# DDR3.net
KiCad netlist of a schematic drawn in Altium Designer
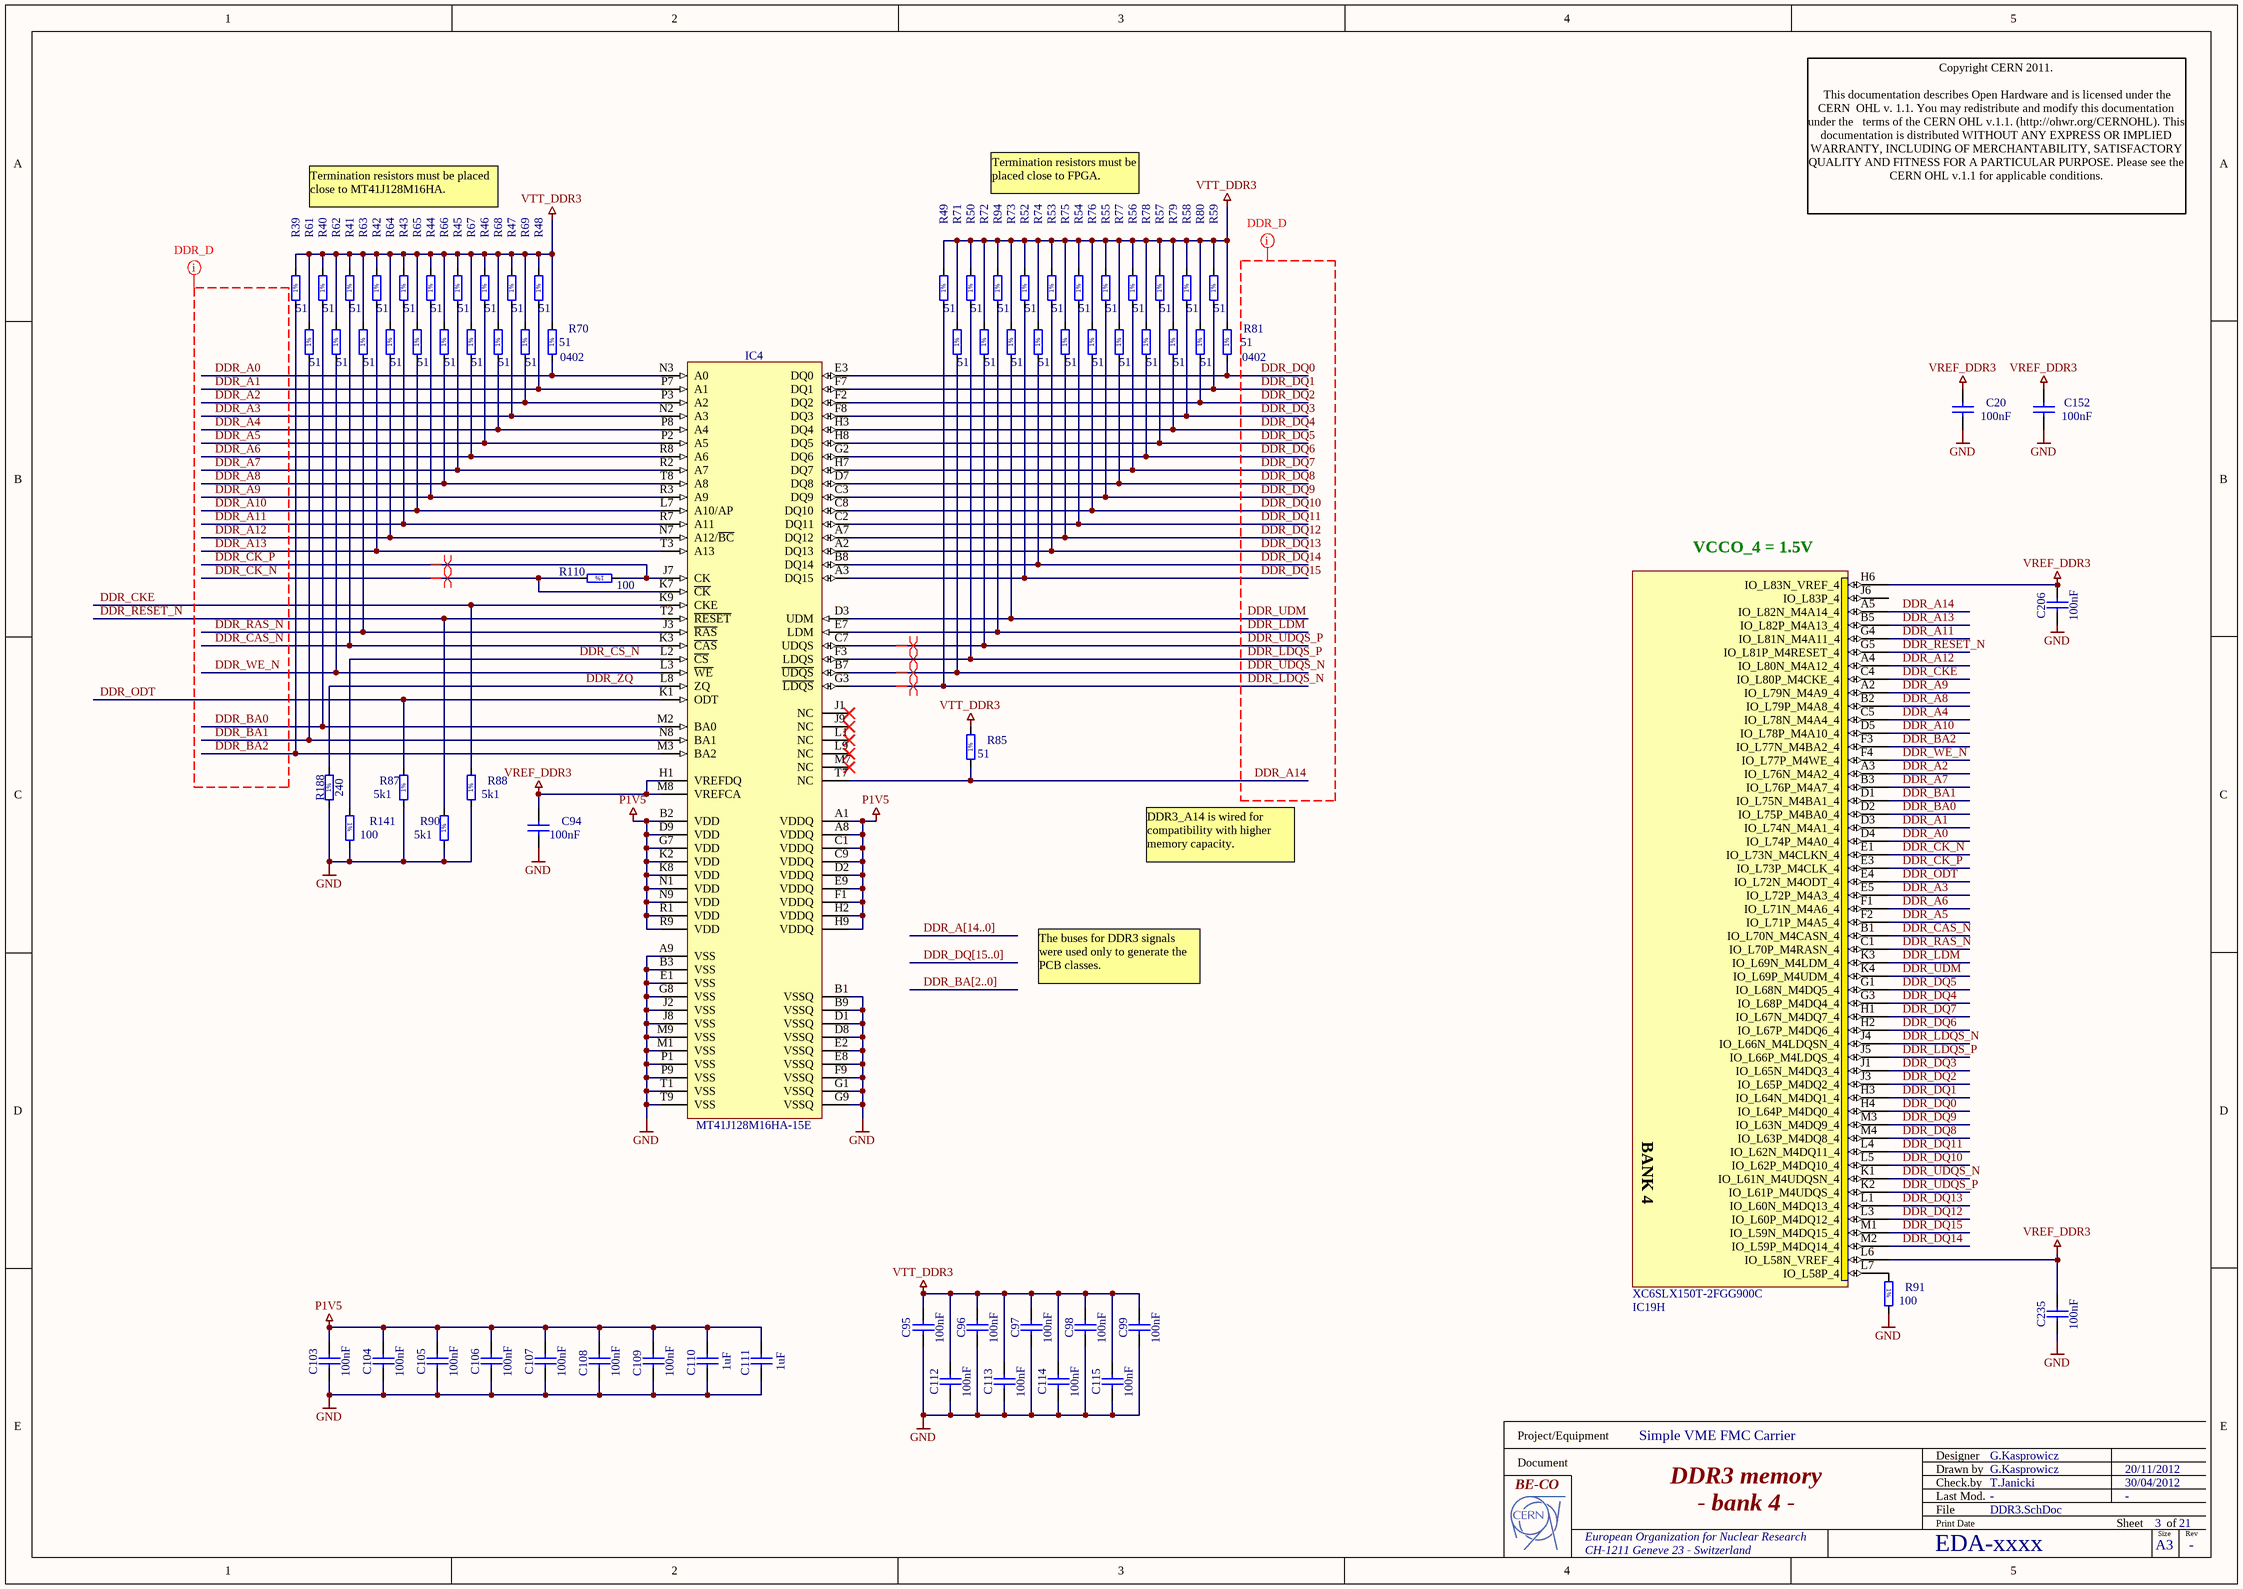
[diagram p0: DDR3.SchDoc]

(export (version "E")
  (design (tool "Eeschema 10.0.6"))
  (components
    (comp (ref "C20")
      (value "100nF")
      (footprint "CAPC1005X55N")
      (description "Non-polarised capacitor")
      (fields
        (field (name "PART NUMBER") "CC0402_100NF_16V_10%_X7R")
        (field (name "VOLTAGE") "16V")
        (field (name "AUTHOR") "CERN DEM JLC")
      )
      (libsource (lib "Capacitors") (part "Capacitor - non polarized"))
    )
    (comp (ref "C94")
      (value "100nF")
      (footprint "CAPC1005X55N")
      (description "Non-polarised capacitor")
      (fields
        (field (name "PART NUMBER") "CC0402_100NF_16V_10%_X7R")
        (field (name "VOLTAGE") "16V")
        (field (name "AUTHOR") "CERN DEM JLC")
      )
      (libsource (lib "Capacitors") (part "Capacitor - non polarized"))
    )
    (comp (ref "C95")
      (value "100nF")
      (footprint "CAPC1005X55N")
      (description "Non-polarised capacitor")
      (fields
        (field (name "PART NUMBER") "CC0402_100NF_16V_10%_X7R")
        (field (name "VOLTAGE") "16V")
        (field (name "AUTHOR") "CERN DEM JLC")
      )
      (libsource (lib "Capacitors") (part "Capacitor - non polarized"))
    )
    (comp (ref "C96")
      (value "100nF")
      (footprint "CAPC1005X55N")
      (description "Non-polarised capacitor")
      (fields
        (field (name "PART NUMBER") "CC0402_100NF_16V_10%_X7R")
        (field (name "VOLTAGE") "16V")
        (field (name "AUTHOR") "CERN DEM JLC")
      )
      (libsource (lib "Capacitors") (part "Capacitor - non polarized"))
    )
    (comp (ref "C97")
      (value "100nF")
      (footprint "CAPC1005X55N")
      (description "Non-polarised capacitor")
      (fields
        (field (name "PART NUMBER") "CC0402_100NF_16V_10%_X7R")
        (field (name "VOLTAGE") "16V")
        (field (name "AUTHOR") "CERN DEM JLC")
      )
      (libsource (lib "Capacitors") (part "Capacitor - non polarized"))
    )
    (comp (ref "C98")
      (value "100nF")
      (footprint "CAPC1005X55N")
      (description "Non-polarised capacitor")
      (fields
        (field (name "PART NUMBER") "CC0402_100NF_16V_10%_X7R")
        (field (name "VOLTAGE") "16V")
        (field (name "AUTHOR") "CERN DEM JLC")
      )
      (libsource (lib "Capacitors") (part "Capacitor - non polarized"))
    )
    (comp (ref "C99")
      (value "100nF")
      (footprint "CAPC1005X55N")
      (description "Non-polarised capacitor")
      (fields
        (field (name "PART NUMBER") "CC0402_100NF_16V_10%_X7R")
        (field (name "VOLTAGE") "16V")
        (field (name "AUTHOR") "CERN DEM JLC")
      )
      (libsource (lib "Capacitors") (part "Capacitor - non polarized"))
    )
    (comp (ref "C103")
      (value "100nF")
      (footprint "CAPC1005X55N")
      (description "Non-polarised capacitor")
      (fields
        (field (name "PART NUMBER") "CC0402_100NF_16V_10%_X7R")
        (field (name "VOLTAGE") "16V")
        (field (name "AUTHOR") "CERN DEM JLC")
      )
      (libsource (lib "Capacitors") (part "Capacitor - non polarized"))
    )
    (comp (ref "C104")
      (value "100nF")
      (footprint "CAPC1005X55N")
      (description "Non-polarised capacitor")
      (fields
        (field (name "PART NUMBER") "CC0402_100NF_16V_10%_X7R")
        (field (name "VOLTAGE") "16V")
        (field (name "AUTHOR") "CERN DEM JLC")
      )
      (libsource (lib "Capacitors") (part "Capacitor - non polarized"))
    )
    (comp (ref "C105")
      (value "100nF")
      (footprint "CAPC1005X55N")
      (description "Non-polarised capacitor")
      (fields
        (field (name "PART NUMBER") "CC0402_100NF_16V_10%_X7R")
        (field (name "VOLTAGE") "16V")
        (field (name "AUTHOR") "CERN DEM JLC")
      )
      (libsource (lib "Capacitors") (part "Capacitor - non polarized"))
    )
    (comp (ref "C106")
      (value "100nF")
      (footprint "CAPC1005X55N")
      (description "Non-polarised capacitor")
      (fields
        (field (name "PART NUMBER") "CC0402_100NF_16V_10%_X7R")
        (field (name "VOLTAGE") "16V")
        (field (name "AUTHOR") "CERN DEM JLC")
      )
      (libsource (lib "Capacitors") (part "Capacitor - non polarized"))
    )
    (comp (ref "C107")
      (value "100nF")
      (footprint "CAPC1005X55N")
      (description "Non-polarised capacitor")
      (fields
        (field (name "PART NUMBER") "CC0402_100NF_16V_10%_X7R")
        (field (name "VOLTAGE") "16V")
        (field (name "AUTHOR") "CERN DEM JLC")
      )
      (libsource (lib "Capacitors") (part "Capacitor - non polarized"))
    )
    (comp (ref "C108")
      (value "100nF")
      (footprint "CAPC1005X55N")
      (description "Non-polarised capacitor")
      (fields
        (field (name "PART NUMBER") "CC0402_100NF_16V_10%_X7R")
        (field (name "VOLTAGE") "16V")
        (field (name "AUTHOR") "CERN DEM JLC")
      )
      (libsource (lib "Capacitors") (part "Capacitor - non polarized"))
    )
    (comp (ref "C109")
      (value "100nF")
      (footprint "CAPC1005X55N")
      (description "Non-polarised capacitor")
      (fields
        (field (name "PART NUMBER") "CC0402_100NF_16V_10%_X7R")
        (field (name "VOLTAGE") "16V")
        (field (name "AUTHOR") "CERN DEM JLC")
      )
      (libsource (lib "Capacitors") (part "Capacitor - non polarized"))
    )
    (comp (ref "C110")
      (value "1uF")
      (footprint "CAPC1608X87N")
      (description "Non-polarised capacitor")
      (fields
        (field (name "PART NUMBER") "CC0603_1UF_16V_10%_X7R")
        (field (name "VOLTAGE") "16V")
        (field (name "AUTHOR") "CERN DEM JLC")
      )
      (libsource (lib "Capacitors") (part "Capacitor - non polarized"))
    )
    (comp (ref "C111")
      (value "1uF")
      (footprint "CAPC1608X87N")
      (description "Non-polarised capacitor")
      (fields
        (field (name "PART NUMBER") "CC0603_1UF_16V_10%_X7R")
        (field (name "VOLTAGE") "16V")
        (field (name "AUTHOR") "CERN DEM JLC")
      )
      (libsource (lib "Capacitors") (part "Capacitor - non polarized"))
    )
    (comp (ref "C112")
      (value "100nF")
      (footprint "CAPC1005X55N")
      (description "Non-polarised capacitor")
      (fields
        (field (name "PART NUMBER") "CC0402_100NF_16V_10%_X7R")
        (field (name "VOLTAGE") "16V")
        (field (name "AUTHOR") "CERN DEM JLC")
      )
      (libsource (lib "Capacitors") (part "Capacitor - non polarized"))
    )
    (comp (ref "C113")
      (value "100nF")
      (footprint "CAPC1005X55N")
      (description "Non-polarised capacitor")
      (fields
        (field (name "PART NUMBER") "CC0402_100NF_16V_10%_X7R")
        (field (name "VOLTAGE") "16V")
        (field (name "AUTHOR") "CERN DEM JLC")
      )
      (libsource (lib "Capacitors") (part "Capacitor - non polarized"))
    )
    (comp (ref "C114")
      (value "100nF")
      (footprint "CAPC1005X55N")
      (description "Non-polarised capacitor")
      (fields
        (field (name "PART NUMBER") "CC0402_100NF_16V_10%_X7R")
        (field (name "VOLTAGE") "16V")
        (field (name "AUTHOR") "CERN DEM JLC")
      )
      (libsource (lib "Capacitors") (part "Capacitor - non polarized"))
    )
    (comp (ref "C115")
      (value "100nF")
      (footprint "CAPC1005X55N")
      (description "Non-polarised capacitor")
      (fields
        (field (name "PART NUMBER") "CC0402_100NF_16V_10%_X7R")
        (field (name "VOLTAGE") "16V")
        (field (name "AUTHOR") "CERN DEM JLC")
      )
      (libsource (lib "Capacitors") (part "Capacitor - non polarized"))
    )
    (comp (ref "C152")
      (value "100nF")
      (footprint "CAPC1005X55N")
      (description "Non-polarised capacitor")
      (fields
        (field (name "PART NUMBER") "CC0402_100NF_16V_10%_X7R")
        (field (name "VOLTAGE") "16V")
        (field (name "AUTHOR") "CERN DEM JLC")
      )
      (libsource (lib "Capacitors") (part "Capacitor - non polarized"))
    )
    (comp (ref "C206")
      (value "100nF")
      (footprint "CAPC1005X55N")
      (description "Non-polarised capacitor")
      (fields
        (field (name "PART NUMBER") "CC0402_100NF_16V_10%_X7R")
        (field (name "VOLTAGE") "16V")
        (field (name "AUTHOR") "CERN DEM JLC")
      )
      (libsource (lib "Capacitors") (part "Capacitor - non polarized"))
    )
    (comp (ref "C235")
      (value "100nF")
      (footprint "CAPC1005X55N")
      (description "Non-polarised capacitor")
      (fields
        (field (name "PART NUMBER") "CC0402_100NF_16V_10%_X7R")
        (field (name "VOLTAGE") "16V")
        (field (name "AUTHOR") "CERN DEM JLC")
      )
      (libsource (lib "Capacitors") (part "Capacitor - non polarized"))
    )
    (comp (ref "IC4")
      (value "MT41J128M16HA-15E")
      (footprint "BGA96C80P9X16_900X1400X120")
      (description "16 Meg x 16 x 8 Banks DDR3 SDRAM")
      (fields (field (name "MANUFACTURER") "MICRON TECHNOLOGY") (field (name "AUTHOR") "CERN DEM JLC"))
      (libsource (lib "ICs And Semiconductors") (part "MT41J128M16HA"))
    )
    (comp (ref "IC19")
      (value "XC6SLX150T-2FGG900C")
      (footprint "BGA900C100P30X30_3100X3100X260")
      (description "SPARTAN-6, FPGA, 900-Ball BGA, Commercial Grade, Pb-Free")
      (fields (field (name "MANUFACTURER") "XILINX") (field (name "AUTHOR") "CERN DEM JLC"))
      (libsource (lib "ICs And Semiconductors") (part "XC6SLX150T-2FGG900C"))
    )
    (comp (ref "R39")
      (value "51")
      (footprint "RESC1005X40N")
      (description "Resistor - 1%")
      (fields
        (field (name "PART NUMBER") "R0402_51R_1%_0.0625W_100PPM")
        (field (name "POWER") "0.0625W")
        (field (name "AUTHOR") "CERN DEM JLC")
      )
      (libsource (lib "Resistors") (part "Resistor - 1%"))
    )
    (comp (ref "R40")
      (value "51")
      (footprint "RESC1005X40N")
      (description "Resistor - 1%")
      (fields
        (field (name "PART NUMBER") "R0402_51R_1%_0.0625W_100PPM")
        (field (name "POWER") "0.0625W")
        (field (name "AUTHOR") "CERN DEM JLC")
      )
      (libsource (lib "Resistors") (part "Resistor - 1%"))
    )
    (comp (ref "R41")
      (value "51")
      (footprint "RESC1005X40N")
      (description "Resistor - 1%")
      (fields
        (field (name "PART NUMBER") "R0402_51R_1%_0.0625W_100PPM")
        (field (name "POWER") "0.0625W")
        (field (name "AUTHOR") "CERN DEM JLC")
      )
      (libsource (lib "Resistors") (part "Resistor - 1%"))
    )
    (comp (ref "R42")
      (value "51")
      (footprint "RESC1005X40N")
      (description "Resistor - 1%")
      (fields
        (field (name "PART NUMBER") "R0402_51R_1%_0.0625W_100PPM")
        (field (name "POWER") "0.0625W")
        (field (name "AUTHOR") "CERN DEM JLC")
      )
      (libsource (lib "Resistors") (part "Resistor - 1%"))
    )
    (comp (ref "R43")
      (value "51")
      (footprint "RESC1005X40N")
      (description "Resistor - 1%")
      (fields
        (field (name "PART NUMBER") "R0402_51R_1%_0.0625W_100PPM")
        (field (name "POWER") "0.0625W")
        (field (name "AUTHOR") "CERN DEM JLC")
      )
      (libsource (lib "Resistors") (part "Resistor - 1%"))
    )
    (comp (ref "R44")
      (value "51")
      (footprint "RESC1005X40N")
      (description "Resistor - 1%")
      (fields
        (field (name "PART NUMBER") "R0402_51R_1%_0.0625W_100PPM")
        (field (name "POWER") "0.0625W")
        (field (name "AUTHOR") "CERN DEM JLC")
      )
      (libsource (lib "Resistors") (part "Resistor - 1%"))
    )
    (comp (ref "R45")
      (value "51")
      (footprint "RESC1005X40N")
      (description "Resistor - 1%")
      (fields
        (field (name "PART NUMBER") "R0402_51R_1%_0.0625W_100PPM")
        (field (name "POWER") "0.0625W")
        (field (name "AUTHOR") "CERN DEM JLC")
      )
      (libsource (lib "Resistors") (part "Resistor - 1%"))
    )
    (comp (ref "R46")
      (value "51")
      (footprint "RESC1005X40N")
      (description "Resistor - 1%")
      (fields
        (field (name "PART NUMBER") "R0402_51R_1%_0.0625W_100PPM")
        (field (name "POWER") "0.0625W")
        (field (name "AUTHOR") "CERN DEM JLC")
      )
      (libsource (lib "Resistors") (part "Resistor - 1%"))
    )
    (comp (ref "R47")
      (value "51")
      (footprint "RESC1005X40N")
      (description "Resistor - 1%")
      (fields
        (field (name "PART NUMBER") "R0402_51R_1%_0.0625W_100PPM")
        (field (name "POWER") "0.0625W")
        (field (name "AUTHOR") "CERN DEM JLC")
      )
      (libsource (lib "Resistors") (part "Resistor - 1%"))
    )
    (comp (ref "R48")
      (value "51")
      (footprint "RESC1005X40N")
      (description "Resistor - 1%")
      (fields
        (field (name "PART NUMBER") "R0402_51R_1%_0.0625W_100PPM")
        (field (name "POWER") "0.0625W")
        (field (name "AUTHOR") "CERN DEM JLC")
      )
      (libsource (lib "Resistors") (part "Resistor - 1%"))
    )
    (comp (ref "R49")
      (value "51")
      (footprint "RESC1005X40N")
      (description "Resistor - 1%")
      (fields
        (field (name "PART NUMBER") "R0402_51R_1%_0.0625W_100PPM")
        (field (name "POWER") "0.0625W")
        (field (name "AUTHOR") "CERN DEM JLC")
      )
      (libsource (lib "Resistors") (part "Resistor - 1%"))
    )
    (comp (ref "R50")
      (value "51")
      (footprint "RESC1005X40N")
      (description "Resistor - 1%")
      (fields
        (field (name "PART NUMBER") "R0402_51R_1%_0.0625W_100PPM")
        (field (name "POWER") "0.0625W")
        (field (name "AUTHOR") "CERN DEM JLC")
      )
      (libsource (lib "Resistors") (part "Resistor - 1%"))
    )
    (comp (ref "R52")
      (value "51")
      (footprint "RESC1005X40N")
      (description "Resistor - 1%")
      (fields
        (field (name "PART NUMBER") "R0402_51R_1%_0.0625W_100PPM")
        (field (name "POWER") "0.0625W")
        (field (name "AUTHOR") "CERN DEM JLC")
      )
      (libsource (lib "Resistors") (part "Resistor - 1%"))
    )
    (comp (ref "R53")
      (value "51")
      (footprint "RESC1005X40N")
      (description "Resistor - 1%")
      (fields
        (field (name "PART NUMBER") "R0402_51R_1%_0.0625W_100PPM")
        (field (name "POWER") "0.0625W")
        (field (name "AUTHOR") "CERN DEM JLC")
      )
      (libsource (lib "Resistors") (part "Resistor - 1%"))
    )
    (comp (ref "R54")
      (value "51")
      (footprint "RESC1005X40N")
      (description "Resistor - 1%")
      (fields
        (field (name "PART NUMBER") "R0402_51R_1%_0.0625W_100PPM")
        (field (name "POWER") "0.0625W")
        (field (name "AUTHOR") "CERN DEM JLC")
      )
      (libsource (lib "Resistors") (part "Resistor - 1%"))
    )
    (comp (ref "R55")
      (value "51")
      (footprint "RESC1005X40N")
      (description "Resistor - 1%")
      (fields
        (field (name "PART NUMBER") "R0402_51R_1%_0.0625W_100PPM")
        (field (name "POWER") "0.0625W")
        (field (name "AUTHOR") "CERN DEM JLC")
      )
      (libsource (lib "Resistors") (part "Resistor - 1%"))
    )
    (comp (ref "R56")
      (value "51")
      (footprint "RESC1005X40N")
      (description "Resistor - 1%")
      (fields
        (field (name "PART NUMBER") "R0402_51R_1%_0.0625W_100PPM")
        (field (name "POWER") "0.0625W")
        (field (name "AUTHOR") "CERN DEM JLC")
      )
      (libsource (lib "Resistors") (part "Resistor - 1%"))
    )
    (comp (ref "R57")
      (value "51")
      (footprint "RESC1005X40N")
      (description "Resistor - 1%")
      (fields
        (field (name "PART NUMBER") "R0402_51R_1%_0.0625W_100PPM")
        (field (name "POWER") "0.0625W")
        (field (name "AUTHOR") "CERN DEM JLC")
      )
      (libsource (lib "Resistors") (part "Resistor - 1%"))
    )
    (comp (ref "R58")
      (value "51")
      (footprint "RESC1005X40N")
      (description "Resistor - 1%")
      (fields
        (field (name "PART NUMBER") "R0402_51R_1%_0.0625W_100PPM")
        (field (name "POWER") "0.0625W")
        (field (name "AUTHOR") "CERN DEM JLC")
      )
      (libsource (lib "Resistors") (part "Resistor - 1%"))
    )
    (comp (ref "R59")
      (value "51")
      (footprint "RESC1005X40N")
      (description "Resistor - 1%")
      (fields
        (field (name "PART NUMBER") "R0402_51R_1%_0.0625W_100PPM")
        (field (name "POWER") "0.0625W")
        (field (name "AUTHOR") "CERN DEM JLC")
      )
      (libsource (lib "Resistors") (part "Resistor - 1%"))
    )
    (comp (ref "R61")
      (value "51")
      (footprint "RESC1005X40N")
      (description "Resistor - 1%")
      (fields
        (field (name "PART NUMBER") "R0402_51R_1%_0.0625W_100PPM")
        (field (name "POWER") "0.0625W")
        (field (name "AUTHOR") "CERN DEM JLC")
      )
      (libsource (lib "Resistors") (part "Resistor - 1%"))
    )
    (comp (ref "R62")
      (value "51")
      (footprint "RESC1005X40N")
      (description "Resistor - 1%")
      (fields
        (field (name "PART NUMBER") "R0402_51R_1%_0.0625W_100PPM")
        (field (name "POWER") "0.0625W")
        (field (name "AUTHOR") "CERN DEM JLC")
      )
      (libsource (lib "Resistors") (part "Resistor - 1%"))
    )
    (comp (ref "R63")
      (value "51")
      (footprint "RESC1005X40N")
      (description "Resistor - 1%")
      (fields
        (field (name "PART NUMBER") "R0402_51R_1%_0.0625W_100PPM")
        (field (name "POWER") "0.0625W")
        (field (name "AUTHOR") "CERN DEM JLC")
      )
      (libsource (lib "Resistors") (part "Resistor - 1%"))
    )
    (comp (ref "R64")
      (value "51")
      (footprint "RESC1005X40N")
      (description "Resistor - 1%")
      (fields
        (field (name "PART NUMBER") "R0402_51R_1%_0.0625W_100PPM")
        (field (name "POWER") "0.0625W")
        (field (name "AUTHOR") "CERN DEM JLC")
      )
      (libsource (lib "Resistors") (part "Resistor - 1%"))
    )
    (comp (ref "R65")
      (value "51")
      (footprint "RESC1005X40N")
      (description "Resistor - 1%")
      (fields
        (field (name "PART NUMBER") "R0402_51R_1%_0.0625W_100PPM")
        (field (name "POWER") "0.0625W")
        (field (name "AUTHOR") "CERN DEM JLC")
      )
      (libsource (lib "Resistors") (part "Resistor - 1%"))
    )
    (comp (ref "R66")
      (value "51")
      (footprint "RESC1005X40N")
      (description "Resistor - 1%")
      (fields
        (field (name "PART NUMBER") "R0402_51R_1%_0.0625W_100PPM")
        (field (name "POWER") "0.0625W")
        (field (name "AUTHOR") "CERN DEM JLC")
      )
      (libsource (lib "Resistors") (part "Resistor - 1%"))
    )
    (comp (ref "R67")
      (value "51")
      (footprint "RESC1005X40N")
      (description "Resistor - 1%")
      (fields
        (field (name "PART NUMBER") "R0402_51R_1%_0.0625W_100PPM")
        (field (name "POWER") "0.0625W")
        (field (name "AUTHOR") "CERN DEM JLC")
      )
      (libsource (lib "Resistors") (part "Resistor - 1%"))
    )
    (comp (ref "R68")
      (value "51")
      (footprint "RESC1005X40N")
      (description "Resistor - 1%")
      (fields
        (field (name "PART NUMBER") "R0402_51R_1%_0.0625W_100PPM")
        (field (name "POWER") "0.0625W")
        (field (name "AUTHOR") "CERN DEM JLC")
      )
      (libsource (lib "Resistors") (part "Resistor - 1%"))
    )
    (comp (ref "R69")
      (value "51")
      (footprint "RESC1005X40N")
      (description "Resistor - 1%")
      (fields
        (field (name "PART NUMBER") "R0402_51R_1%_0.0625W_100PPM")
        (field (name "POWER") "0.0625W")
        (field (name "AUTHOR") "CERN DEM JLC")
      )
      (libsource (lib "Resistors") (part "Resistor - 1%"))
    )
    (comp (ref "R70")
      (value "51")
      (footprint "RESC1005X40N")
      (description "Resistor - 1%")
      (fields
        (field (name "PART NUMBER") "R0402_51R_1%_0.0625W_100PPM")
        (field (name "POWER") "0.0625W")
        (field (name "CASE") "0402")
        (field (name "AUTHOR") "CERN DEM JLC")
      )
      (libsource (lib "Resistors") (part "Resistor - 1%"))
    )
    (comp (ref "R71")
      (value "51")
      (footprint "RESC1005X40N")
      (description "Resistor - 1%")
      (fields
        (field (name "PART NUMBER") "R0402_51R_1%_0.0625W_100PPM")
        (field (name "POWER") "0.0625W")
        (field (name "AUTHOR") "CERN DEM JLC")
      )
      (libsource (lib "Resistors") (part "Resistor - 1%"))
    )
    (comp (ref "R72")
      (value "51")
      (footprint "RESC1005X40N")
      (description "Resistor - 1%")
      (fields
        (field (name "PART NUMBER") "R0402_51R_1%_0.0625W_100PPM")
        (field (name "POWER") "0.0625W")
        (field (name "AUTHOR") "CERN DEM JLC")
      )
      (libsource (lib "Resistors") (part "Resistor - 1%"))
    )
    (comp (ref "R73")
      (value "51")
      (footprint "RESC1005X40N")
      (description "Resistor - 1%")
      (fields
        (field (name "PART NUMBER") "R0402_51R_1%_0.0625W_100PPM")
        (field (name "POWER") "0.0625W")
        (field (name "AUTHOR") "CERN DEM JLC")
      )
      (libsource (lib "Resistors") (part "Resistor - 1%"))
    )
    (comp (ref "R74")
      (value "51")
      (footprint "RESC1005X40N")
      (description "Resistor - 1%")
      (fields
        (field (name "PART NUMBER") "R0402_51R_1%_0.0625W_100PPM")
        (field (name "POWER") "0.0625W")
        (field (name "AUTHOR") "CERN DEM JLC")
      )
      (libsource (lib "Resistors") (part "Resistor - 1%"))
    )
    (comp (ref "R75")
      (value "51")
      (footprint "RESC1005X40N")
      (description "Resistor - 1%")
      (fields
        (field (name "PART NUMBER") "R0402_51R_1%_0.0625W_100PPM")
        (field (name "POWER") "0.0625W")
        (field (name "AUTHOR") "CERN DEM JLC")
      )
      (libsource (lib "Resistors") (part "Resistor - 1%"))
    )
    (comp (ref "R76")
      (value "51")
      (footprint "RESC1005X40N")
      (description "Resistor - 1%")
      (fields
        (field (name "PART NUMBER") "R0402_51R_1%_0.0625W_100PPM")
        (field (name "POWER") "0.0625W")
        (field (name "AUTHOR") "CERN DEM JLC")
      )
      (libsource (lib "Resistors") (part "Resistor - 1%"))
    )
    (comp (ref "R77")
      (value "51")
      (footprint "RESC1005X40N")
      (description "Resistor - 1%")
      (fields
        (field (name "PART NUMBER") "R0402_51R_1%_0.0625W_100PPM")
        (field (name "POWER") "0.0625W")
        (field (name "AUTHOR") "CERN DEM JLC")
      )
      (libsource (lib "Resistors") (part "Resistor - 1%"))
    )
    (comp (ref "R78")
      (value "51")
      (footprint "RESC1005X40N")
      (description "Resistor - 1%")
      (fields
        (field (name "PART NUMBER") "R0402_51R_1%_0.0625W_100PPM")
        (field (name "POWER") "0.0625W")
        (field (name "AUTHOR") "CERN DEM JLC")
      )
      (libsource (lib "Resistors") (part "Resistor - 1%"))
    )
    (comp (ref "R79")
      (value "51")
      (footprint "RESC1005X40N")
      (description "Resistor - 1%")
      (fields
        (field (name "PART NUMBER") "R0402_51R_1%_0.0625W_100PPM")
        (field (name "POWER") "0.0625W")
        (field (name "AUTHOR") "CERN DEM JLC")
      )
      (libsource (lib "Resistors") (part "Resistor - 1%"))
    )
    (comp (ref "R80")
      (value "51")
      (footprint "RESC1005X40N")
      (description "Resistor - 1%")
      (fields
        (field (name "PART NUMBER") "R0402_51R_1%_0.0625W_100PPM")
        (field (name "POWER") "0.0625W")
        (field (name "AUTHOR") "CERN DEM JLC")
      )
      (libsource (lib "Resistors") (part "Resistor - 1%"))
    )
    (comp (ref "R81")
      (value "51")
      (footprint "RESC1005X40N")
      (description "Resistor - 1%")
      (fields
        (field (name "PART NUMBER") "R0402_51R_1%_0.0625W_100PPM")
        (field (name "POWER") "0.0625W")
        (field (name "CASE") "0402")
        (field (name "AUTHOR") "CERN DEM JLC")
      )
      (libsource (lib "Resistors") (part "Resistor - 1%"))
    )
    (comp (ref "R85")
      (value "51")
      (footprint "RESC1005X40N")
      (description "Resistor - 1%")
      (fields
        (field (name "PART NUMBER") "R0402_51R_1%_0.0625W_100PPM")
        (field (name "POWER") "0.0625W")
        (field (name "AUTHOR") "CERN DEM JLC")
      )
      (libsource (lib "Resistors") (part "Resistor - 1%"))
    )
    (comp (ref "R87")
      (value "5k1")
      (footprint "RESC1608X55N")
      (description "Resistor - 1%")
      (fields
        (field (name "PART NUMBER") "R0603_5K1_1%_0.1W_100PPM")
        (field (name "POWER") "0.1W")
        (field (name "AUTHOR") "CERN DEM JLC")
      )
      (libsource (lib "Resistors") (part "Resistor - 1%"))
    )
    (comp (ref "R88")
      (value "5k1")
      (footprint "RESC1608X55N")
      (description "Resistor - 1%")
      (fields
        (field (name "PART NUMBER") "R0603_5K1_1%_0.1W_100PPM")
        (field (name "POWER") "0.1W")
        (field (name "AUTHOR") "CERN DEM JLC")
      )
      (libsource (lib "Resistors") (part "Resistor - 1%"))
    )
    (comp (ref "R90")
      (value "5k1")
      (footprint "RESC1608X55N")
      (description "Resistor - 1%")
      (fields
        (field (name "PART NUMBER") "R0603_5K1_1%_0.1W_100PPM")
        (field (name "POWER") "0.1W")
        (field (name "AUTHOR") "CERN DEM JLC")
      )
      (libsource (lib "Resistors") (part "Resistor - 1%"))
    )
    (comp (ref "R91")
      (value "100")
      (footprint "RESC1608X55N")
      (description "Resistor - 1%")
      (fields
        (field (name "PART NUMBER") "R0603_100R_1%_0.1W_100PPM")
        (field (name "POWER") "0.1W")
        (field (name "AUTHOR") "CERN DEM JLC")
      )
      (libsource (lib "Resistors") (part "Resistor - 1%"))
    )
    (comp (ref "R94")
      (value "51")
      (footprint "RESC1005X40N")
      (description "Resistor - 1%")
      (fields
        (field (name "PART NUMBER") "R0402_51R_1%_0.0625W_100PPM")
        (field (name "POWER") "0.0625W")
        (field (name "AUTHOR") "CERN DEM JLC")
      )
      (libsource (lib "Resistors") (part "Resistor - 1%"))
    )
    (comp (ref "R110")
      (value "100")
      (footprint "RESC1608X55N")
      (description "Resistor - 1%")
      (fields
        (field (name "PART NUMBER") "R0603_100R_1%_0.1W_100PPM")
        (field (name "POWER") "0.1W")
        (field (name "AUTHOR") "CERN DEM JLC")
      )
      (libsource (lib "Resistors") (part "Resistor - 1%"))
    )
    (comp (ref "R141")
      (value "100")
      (footprint "RESC1608X55N")
      (description "Resistor - 1%")
      (fields
        (field (name "PART NUMBER") "R0603_100R_1%_0.1W_100PPM")
        (field (name "POWER") "0.1W")
        (field (name "AUTHOR") "CERN DEM JLC")
      )
      (libsource (lib "Resistors") (part "Resistor - 1%"))
    )
    (comp (ref "R188")
      (value "240")
      (footprint "RESC1608X55N")
      (description "Resistor - 1%")
      (fields
        (field (name "PART NUMBER") "R0603_240R_1%_0.1W_100PPM")
        (field (name "POWER") "0.1W")
        (field (name "AUTHOR") "CERN DEM JLC")
      )
      (libsource (lib "Resistors") (part "Resistor - 1%"))
    )
  )
  (nets
    (net (code "1") (name "/DDR_A0") (class "Default")
      (node (ref "IC19") (pin "D4") (pinfunction "IO_L74P_M4A0_4_D4") (pintype "bidirectional"))
      (node (ref "IC4") (pin "N3") (pinfunction "A0_N3") (pintype "input"))
      (node (ref "R70") (pin "1") (pinfunction "1_1") (pintype "passive"))
    )
    (net (code "2") (name "/DDR_A1") (class "Default")
      (node (ref "IC19") (pin "D3") (pinfunction "IO_L74N_M4A1_4_D3") (pintype "bidirectional"))
      (node (ref "IC4") (pin "P7") (pinfunction "A1_P7") (pintype "input"))
      (node (ref "R48") (pin "1") (pinfunction "1_1") (pintype "passive"))
    )
    (net (code "3") (name "/DDR_A2") (class "Default")
      (node (ref "IC19") (pin "A3") (pinfunction "IO_L76N_M4A2_4_A3") (pintype "bidirectional"))
      (node (ref "IC4") (pin "P3") (pinfunction "A2_P3") (pintype "input"))
      (node (ref "R69") (pin "1") (pinfunction "1_1") (pintype "passive"))
    )
    (net (code "4") (name "/DDR_A3") (class "Default")
      (node (ref "IC19") (pin "E5") (pinfunction "IO_L72P_M4A3_4_E5") (pintype "bidirectional"))
      (node (ref "IC4") (pin "N2") (pinfunction "A3_N2") (pintype "input"))
      (node (ref "R47") (pin "1") (pinfunction "1_1") (pintype "passive"))
    )
    (net (code "5") (name "/DDR_A4") (class "Default")
      (node (ref "IC19") (pin "C5") (pinfunction "IO_L78N_M4A4_4_C5") (pintype "bidirectional"))
      (node (ref "IC4") (pin "P8") (pinfunction "A4_P8") (pintype "input"))
      (node (ref "R68") (pin "1") (pinfunction "1_1") (pintype "passive"))
    )
    (net (code "6") (name "/DDR_A5") (class "Default")
      (node (ref "IC19") (pin "F2") (pinfunction "IO_L71P_M4A5_4_F2") (pintype "bidirectional"))
      (node (ref "IC4") (pin "P2") (pinfunction "A5_P2") (pintype "input"))
      (node (ref "R46") (pin "1") (pinfunction "1_1") (pintype "passive"))
    )
    (net (code "7") (name "/DDR_A6") (class "Default")
      (node (ref "IC19") (pin "F1") (pinfunction "IO_L71N_M4A6_4_F1") (pintype "bidirectional"))
      (node (ref "IC4") (pin "R8") (pinfunction "A6_R8") (pintype "input"))
      (node (ref "R67") (pin "1") (pinfunction "1_1") (pintype "passive"))
    )
    (net (code "8") (name "/DDR_A7") (class "Default")
      (node (ref "IC19") (pin "B3") (pinfunction "IO_L76P_M4A7_4_B3") (pintype "bidirectional"))
      (node (ref "IC4") (pin "R2") (pinfunction "A7_R2") (pintype "input"))
      (node (ref "R45") (pin "1") (pinfunction "1_1") (pintype "passive"))
    )
    (net (code "9") (name "/DDR_A8") (class "Default")
      (node (ref "IC19") (pin "B2") (pinfunction "IO_L79P_M4A8_4_B2") (pintype "bidirectional"))
      (node (ref "IC4") (pin "T8") (pinfunction "A8_T8") (pintype "input"))
      (node (ref "R66") (pin "1") (pinfunction "1_1") (pintype "passive"))
    )
    (net (code "10") (name "/DDR_A9") (class "Default")
      (node (ref "IC19") (pin "A2") (pinfunction "IO_L79N_M4A9_4_A2") (pintype "bidirectional"))
      (node (ref "IC4") (pin "R3") (pinfunction "A9_R3") (pintype "input"))
      (node (ref "R44") (pin "1") (pinfunction "1_1") (pintype "passive"))
    )
    (net (code "11") (name "/DDR_A10") (class "Default")
      (node (ref "IC19") (pin "D5") (pinfunction "IO_L78P_M4A10_4_D5") (pintype "bidirectional"))
      (node (ref "IC4") (pin "L7") (pinfunction "A10/AP_L7") (pintype "input"))
      (node (ref "R65") (pin "1") (pinfunction "1_1") (pintype "passive"))
    )
    (net (code "12") (name "/DDR_A11") (class "Default")
      (node (ref "IC19") (pin "G4") (pinfunction "IO_L81N_M4A11_4_G4") (pintype "bidirectional"))
      (node (ref "IC4") (pin "R7") (pinfunction "A11_R7") (pintype "input"))
      (node (ref "R43") (pin "1") (pinfunction "1_1") (pintype "passive"))
    )
    (net (code "13") (name "/DDR_A12") (class "Default")
      (node (ref "IC19") (pin "A4") (pinfunction "IO_L80N_M4A12_4_A4") (pintype "bidirectional"))
      (node (ref "IC4") (pin "N7") (pinfunction "A12/~{BC}_N7") (pintype "input"))
      (node (ref "R64") (pin "1") (pinfunction "1_1") (pintype "passive"))
    )
    (net (code "14") (name "/DDR_A13") (class "Default")
      (node (ref "IC19") (pin "B5") (pinfunction "IO_L82P_M4A13_4_B5") (pintype "bidirectional"))
      (node (ref "IC4") (pin "T3") (pinfunction "A13_T3") (pintype "input"))
      (node (ref "R42") (pin "1") (pinfunction "1_1") (pintype "passive"))
    )
    (net (code "15") (name "/DDR_A14") (class "Default")
      (node (ref "IC19") (pin "A5") (pinfunction "IO_L82N_M4A14_4_A5") (pintype "bidirectional"))
      (node (ref "IC4") (pin "T7") (pinfunction "NC_T7") (pintype "passive"))
      (node (ref "R85") (pin "1") (pinfunction "1_1") (pintype "passive"))
    )
    (net (code "17") (name "/DDR_BA0") (class "Default")
      (node (ref "IC19") (pin "D2") (pinfunction "IO_L75P_M4BA0_4_D2") (pintype "bidirectional"))
      (node (ref "IC4") (pin "M2") (pinfunction "BA0_M2") (pintype "input"))
      (node (ref "R40") (pin "1") (pinfunction "1_1") (pintype "passive"))
    )
    (net (code "18") (name "/DDR_BA1") (class "Default")
      (node (ref "IC19") (pin "D1") (pinfunction "IO_L75N_M4BA1_4_D1") (pintype "bidirectional"))
      (node (ref "IC4") (pin "N8") (pinfunction "BA1_N8") (pintype "input"))
      (node (ref "R61") (pin "1") (pinfunction "1_1") (pintype "passive"))
    )
    (net (code "19") (name "/DDR_BA2") (class "Default")
      (node (ref "IC19") (pin "F3") (pinfunction "IO_L77N_M4BA2_4_F3") (pintype "bidirectional"))
      (node (ref "IC4") (pin "M3") (pinfunction "BA2_M3") (pintype "input"))
      (node (ref "R39") (pin "1") (pinfunction "1_1") (pintype "passive"))
    )
    (net (code "21") (name "/DDR_CAS_N") (class "Default")
      (node (ref "IC19") (pin "B1") (pinfunction "IO_L70N_M4CASN_4_B1") (pintype "bidirectional"))
      (node (ref "IC4") (pin "K3") (pinfunction "CAS_K3") (pintype "input"))
      (node (ref "R41") (pin "1") (pinfunction "1_1") (pintype "passive"))
    )
    (net (code "22") (name "/DDR_CKE") (class "Default")
      (node (ref "IC19") (pin "C4") (pinfunction "IO_L80P_M4CKE_4_C4") (pintype "bidirectional"))
      (node (ref "IC4") (pin "K9") (pinfunction "CKE_K9") (pintype "input"))
      (node (ref "R88") (pin "2") (pinfunction "2_2") (pintype "passive"))
    )
    (net (code "23") (name "/DDR_CK_N") (class "Default")
      (node (ref "IC19") (pin "E1") (pinfunction "IO_L73N_M4CLKN_4_E1") (pintype "bidirectional"))
      (node (ref "IC4") (pin "K7") (pinfunction "CK_K7") (pintype "input"))
      (node (ref "R110") (pin "2") (pinfunction "2_2") (pintype "passive"))
    )
    (net (code "24") (name "/DDR_CK_P") (class "Default")
      (node (ref "IC19") (pin "E3") (pinfunction "IO_L73P_M4CLK_4_E3") (pintype "bidirectional"))
      (node (ref "IC4") (pin "J7") (pinfunction "CK_J7") (pintype "input"))
      (node (ref "R110") (pin "1") (pinfunction "1_1") (pintype "passive"))
    )
    (net (code "25") (name "/DDR_CS_N") (class "Default")
      (node (ref "IC4") (pin "L2") (pinfunction "CS_L2") (pintype "input"))
      (node (ref "R141") (pin "1") (pinfunction "1_1") (pintype "passive"))
    )
    (net (code "26") (name "/DDR_DQ0") (class "Default")
      (node (ref "IC19") (pin "H4") (pinfunction "IO_L64P_M4DQ0_4_H4") (pintype "bidirectional"))
      (node (ref "IC4") (pin "E3") (pinfunction "DQ0_E3") (pintype "bidirectional"))
      (node (ref "R81") (pin "1") (pinfunction "1_1") (pintype "passive"))
    )
    (net (code "27") (name "/DDR_DQ1") (class "Default")
      (node (ref "IC19") (pin "H3") (pinfunction "IO_L64N_M4DQ1_4_H3") (pintype "bidirectional"))
      (node (ref "IC4") (pin "F7") (pinfunction "DQ1_F7") (pintype "bidirectional"))
      (node (ref "R59") (pin "1") (pinfunction "1_1") (pintype "passive"))
    )
    (net (code "28") (name "/DDR_DQ2") (class "Default")
      (node (ref "IC19") (pin "J3") (pinfunction "IO_L65P_M4DQ2_4_J3") (pintype "bidirectional"))
      (node (ref "IC4") (pin "F2") (pinfunction "DQ2_F2") (pintype "bidirectional"))
      (node (ref "R80") (pin "1") (pinfunction "1_1") (pintype "passive"))
    )
    (net (code "29") (name "/DDR_DQ3") (class "Default")
      (node (ref "IC19") (pin "J1") (pinfunction "IO_L65N_M4DQ3_4_J1") (pintype "bidirectional"))
      (node (ref "IC4") (pin "F8") (pinfunction "DQ3_F8") (pintype "bidirectional"))
      (node (ref "R58") (pin "1") (pinfunction "1_1") (pintype "passive"))
    )
    (net (code "30") (name "/DDR_DQ4") (class "Default")
      (node (ref "IC19") (pin "G3") (pinfunction "IO_L68P_M4DQ4_4_G3") (pintype "bidirectional"))
      (node (ref "IC4") (pin "H3") (pinfunction "DQ4_H3") (pintype "bidirectional"))
      (node (ref "R79") (pin "1") (pinfunction "1_1") (pintype "passive"))
    )
    (net (code "31") (name "/DDR_DQ5") (class "Default")
      (node (ref "IC19") (pin "G1") (pinfunction "IO_L68N_M4DQ5_4_G1") (pintype "bidirectional"))
      (node (ref "IC4") (pin "H8") (pinfunction "DQ5_H8") (pintype "bidirectional"))
      (node (ref "R57") (pin "1") (pinfunction "1_1") (pintype "passive"))
    )
    (net (code "32") (name "/DDR_DQ6") (class "Default")
      (node (ref "IC19") (pin "H2") (pinfunction "IO_L67P_M4DQ6_4_H2") (pintype "bidirectional"))
      (node (ref "IC4") (pin "G2") (pinfunction "DQ6_G2") (pintype "bidirectional"))
      (node (ref "R78") (pin "1") (pinfunction "1_1") (pintype "passive"))
    )
    (net (code "33") (name "/DDR_DQ7") (class "Default")
      (node (ref "IC19") (pin "H1") (pinfunction "IO_L67N_M4DQ7_4_H1") (pintype "bidirectional"))
      (node (ref "IC4") (pin "H7") (pinfunction "DQ7_H7") (pintype "bidirectional"))
      (node (ref "R56") (pin "1") (pinfunction "1_1") (pintype "passive"))
    )
    (net (code "34") (name "/DDR_DQ8") (class "Default")
      (node (ref "IC19") (pin "M4") (pinfunction "IO_L63P_M4DQ8_4_M4") (pintype "bidirectional"))
      (node (ref "IC4") (pin "D7") (pinfunction "DQ8_D7") (pintype "bidirectional"))
      (node (ref "R77") (pin "1") (pinfunction "1_1") (pintype "passive"))
    )
    (net (code "35") (name "/DDR_DQ9") (class "Default")
      (node (ref "IC19") (pin "M3") (pinfunction "IO_L63N_M4DQ9_4_M3") (pintype "bidirectional"))
      (node (ref "IC4") (pin "C3") (pinfunction "DQ9_C3") (pintype "bidirectional"))
      (node (ref "R55") (pin "1") (pinfunction "1_1") (pintype "passive"))
    )
    (net (code "36") (name "/DDR_DQ10") (class "Default")
      (node (ref "IC19") (pin "L5") (pinfunction "IO_L62P_M4DQ10_4_L5") (pintype "bidirectional"))
      (node (ref "IC4") (pin "C8") (pinfunction "DQ10_C8") (pintype "bidirectional"))
      (node (ref "R76") (pin "1") (pinfunction "1_1") (pintype "passive"))
    )
    (net (code "37") (name "/DDR_DQ11") (class "Default")
      (node (ref "IC19") (pin "L4") (pinfunction "IO_L62N_M4DQ11_4_L4") (pintype "bidirectional"))
      (node (ref "IC4") (pin "C2") (pinfunction "DQ11_C2") (pintype "bidirectional"))
      (node (ref "R54") (pin "1") (pinfunction "1_1") (pintype "passive"))
    )
    (net (code "38") (name "/DDR_DQ12") (class "Default")
      (node (ref "IC19") (pin "L3") (pinfunction "IO_L60P_M4DQ12_4_L3") (pintype "bidirectional"))
      (node (ref "IC4") (pin "A7") (pinfunction "DQ12_A7") (pintype "bidirectional"))
      (node (ref "R75") (pin "1") (pinfunction "1_1") (pintype "passive"))
    )
    (net (code "39") (name "/DDR_DQ13") (class "Default")
      (node (ref "IC19") (pin "L1") (pinfunction "IO_L60N_M4DQ13_4_L1") (pintype "bidirectional"))
      (node (ref "IC4") (pin "A2") (pinfunction "DQ13_A2") (pintype "bidirectional"))
      (node (ref "R53") (pin "1") (pinfunction "1_1") (pintype "passive"))
    )
    (net (code "40") (name "/DDR_DQ14") (class "Default")
      (node (ref "IC19") (pin "M2") (pinfunction "IO_L59P_M4DQ14_4_M2") (pintype "bidirectional"))
      (node (ref "IC4") (pin "B8") (pinfunction "DQ14_B8") (pintype "bidirectional"))
      (node (ref "R74") (pin "1") (pinfunction "1_1") (pintype "passive"))
    )
    (net (code "41") (name "/DDR_DQ15") (class "Default")
      (node (ref "IC19") (pin "M1") (pinfunction "IO_L59N_M4DQ15_4_M1") (pintype "bidirectional"))
      (node (ref "IC4") (pin "A3") (pinfunction "DQ15_A3") (pintype "bidirectional"))
      (node (ref "R52") (pin "1") (pinfunction "1_1") (pintype "passive"))
    )
    (net (code "43") (name "/DDR_LDM") (class "Default")
      (node (ref "IC19") (pin "K3") (pinfunction "IO_L69N_M4LDM_4_K3") (pintype "bidirectional"))
      (node (ref "IC4") (pin "E7") (pinfunction "LDM_E7") (pintype "input"))
      (node (ref "R94") (pin "1") (pinfunction "1_1") (pintype "passive"))
    )
    (net (code "44") (name "/DDR_LDQS_N") (class "Default")
      (node (ref "IC19") (pin "J4") (pinfunction "IO_L66N_M4LDQSN_4_J4") (pintype "bidirectional"))
      (node (ref "IC4") (pin "G3") (pinfunction "LDQS_G3") (pintype "bidirectional"))
      (node (ref "R49") (pin "1") (pinfunction "1_1") (pintype "passive"))
    )
    (net (code "45") (name "/DDR_LDQS_P") (class "Default")
      (node (ref "IC19") (pin "J5") (pinfunction "IO_L66P_M4LDQS_4_J5") (pintype "bidirectional"))
      (node (ref "IC4") (pin "F3") (pinfunction "LDQS_F3") (pintype "bidirectional"))
      (node (ref "R50") (pin "1") (pinfunction "1_1") (pintype "passive"))
    )
    (net (code "46") (name "/DDR_ODT") (class "Default")
      (node (ref "IC19") (pin "E4") (pinfunction "IO_L72N_M4ODT_4_E4") (pintype "bidirectional"))
      (node (ref "IC4") (pin "K1") (pinfunction "ODT_K1") (pintype "input"))
      (node (ref "R87") (pin "2") (pinfunction "2_2") (pintype "passive"))
    )
    (net (code "47") (name "/DDR_RAS_N") (class "Default")
      (node (ref "IC19") (pin "C1") (pinfunction "IO_L70P_M4RASN_4_C1") (pintype "bidirectional"))
      (node (ref "IC4") (pin "J3") (pinfunction "RAS_J3") (pintype "input"))
      (node (ref "R63") (pin "1") (pinfunction "1_1") (pintype "passive"))
    )
    (net (code "48") (name "/DDR_RESET_N") (class "Default")
      (node (ref "IC19") (pin "G5") (pinfunction "IO_L81P_M4RESET_4_G5") (pintype "bidirectional"))
      (node (ref "IC4") (pin "T2") (pinfunction "RESET_T2") (pintype "input"))
      (node (ref "R90") (pin "2") (pinfunction "2_2") (pintype "passive"))
    )
    (net (code "49") (name "/DDR_UDM") (class "Default")
      (node (ref "IC19") (pin "K4") (pinfunction "IO_L69P_M4UDM_4_K4") (pintype "bidirectional"))
      (node (ref "IC4") (pin "D3") (pinfunction "UDM_D3") (pintype "input"))
      (node (ref "R73") (pin "1") (pinfunction "1_1") (pintype "passive"))
    )
    (net (code "50") (name "/DDR_UDQS_N") (class "Default")
      (node (ref "IC19") (pin "K1") (pinfunction "IO_L61N_M4UDQSN_4_K1") (pintype "bidirectional"))
      (node (ref "IC4") (pin "B7") (pinfunction "UDQS_B7") (pintype "bidirectional"))
      (node (ref "R71") (pin "1") (pinfunction "1_1") (pintype "passive"))
    )
    (net (code "51") (name "/DDR_UDQS_P") (class "Default")
      (node (ref "IC19") (pin "K2") (pinfunction "IO_L61P_M4UDQS_4_K2") (pintype "bidirectional"))
      (node (ref "IC4") (pin "C7") (pinfunction "UDQS_C7") (pintype "bidirectional"))
      (node (ref "R72") (pin "1") (pinfunction "1_1") (pintype "passive"))
    )
    (net (code "52") (name "/DDR_WE_N") (class "Default")
      (node (ref "IC19") (pin "F4") (pinfunction "IO_L77P_M4WE_4_F4") (pintype "bidirectional"))
      (node (ref "IC4") (pin "L3") (pinfunction "WE_L3") (pintype "input"))
      (node (ref "R62") (pin "1") (pinfunction "1_1") (pintype "passive"))
    )
    (net (code "53") (name "/DDR_ZQ") (class "Default")
      (node (ref "IC4") (pin "L8") (pinfunction "ZQ_L8") (pintype "input"))
      (node (ref "R188") (pin "2") (pinfunction "2_2") (pintype "passive"))
    )
    (net (code "54") (name "GND") (class "Default")
      (node (ref "C103") (pin "1") (pinfunction "1_1") (pintype "passive"))
      (node (ref "C104") (pin "1") (pinfunction "1_1") (pintype "passive"))
      (node (ref "C105") (pin "1") (pinfunction "1_1") (pintype "passive"))
      (node (ref "C106") (pin "1") (pinfunction "1_1") (pintype "passive"))
      (node (ref "C107") (pin "1") (pinfunction "1_1") (pintype "passive"))
      (node (ref "C108") (pin "1") (pinfunction "1_1") (pintype "passive"))
      (node (ref "C109") (pin "1") (pinfunction "1_1") (pintype "passive"))
      (node (ref "C110") (pin "1") (pinfunction "1_1") (pintype "passive"))
      (node (ref "C111") (pin "1") (pinfunction "1_1") (pintype "passive"))
      (node (ref "C112") (pin "1") (pinfunction "1_1") (pintype "passive"))
      (node (ref "C113") (pin "1") (pinfunction "1_1") (pintype "passive"))
      (node (ref "C114") (pin "1") (pinfunction "1_1") (pintype "passive"))
      (node (ref "C115") (pin "1") (pinfunction "1_1") (pintype "passive"))
      (node (ref "C152") (pin "1") (pinfunction "1_1") (pintype "passive"))
      (node (ref "C20") (pin "1") (pinfunction "1_1") (pintype "passive"))
      (node (ref "C206") (pin "1") (pinfunction "1_1") (pintype "passive"))
      (node (ref "C235") (pin "1") (pinfunction "1_1") (pintype "passive"))
      (node (ref "C94") (pin "1") (pinfunction "1_1") (pintype "passive"))
      (node (ref "C95") (pin "1") (pinfunction "1_1") (pintype "passive"))
      (node (ref "C96") (pin "1") (pinfunction "1_1") (pintype "passive"))
      (node (ref "C97") (pin "1") (pinfunction "1_1") (pintype "passive"))
      (node (ref "C98") (pin "1") (pinfunction "1_1") (pintype "passive"))
      (node (ref "C99") (pin "1") (pinfunction "1_1") (pintype "passive"))
      (node (ref "IC4") (pin "A9") (pinfunction "VSS_A9") (pintype "power_in"))
      (node (ref "IC4") (pin "B1") (pinfunction "VSSQ_B1") (pintype "power_in"))
      (node (ref "IC4") (pin "B3") (pinfunction "VSS_B3") (pintype "power_in"))
      (node (ref "IC4") (pin "B9") (pinfunction "VSSQ_B9") (pintype "power_in"))
      (node (ref "IC4") (pin "D1") (pinfunction "VSSQ_D1") (pintype "power_in"))
      (node (ref "IC4") (pin "D8") (pinfunction "VSSQ_D8") (pintype "power_in"))
      (node (ref "IC4") (pin "E1") (pinfunction "VSS_E1") (pintype "power_in"))
      (node (ref "IC4") (pin "E2") (pinfunction "VSSQ_E2") (pintype "power_in"))
      (node (ref "IC4") (pin "E8") (pinfunction "VSSQ_E8") (pintype "power_in"))
      (node (ref "IC4") (pin "F9") (pinfunction "VSSQ_F9") (pintype "power_in"))
      (node (ref "IC4") (pin "G1") (pinfunction "VSSQ_G1") (pintype "power_in"))
      (node (ref "IC4") (pin "G8") (pinfunction "VSS_G8") (pintype "power_in"))
      (node (ref "IC4") (pin "G9") (pinfunction "VSSQ_G9") (pintype "power_in"))
      (node (ref "IC4") (pin "J2") (pinfunction "VSS_J2") (pintype "power_in"))
      (node (ref "IC4") (pin "J8") (pinfunction "VSS_J8") (pintype "power_in"))
      (node (ref "IC4") (pin "M1") (pinfunction "VSS_M1") (pintype "power_in"))
      (node (ref "IC4") (pin "M9") (pinfunction "VSS_M9") (pintype "power_in"))
      (node (ref "IC4") (pin "P1") (pinfunction "VSS_P1") (pintype "power_in"))
      (node (ref "IC4") (pin "P9") (pinfunction "VSS_P9") (pintype "power_in"))
      (node (ref "IC4") (pin "T1") (pinfunction "VSS_T1") (pintype "power_in"))
      (node (ref "IC4") (pin "T9") (pinfunction "VSS_T9") (pintype "power_in"))
      (node (ref "R141") (pin "2") (pinfunction "2_2") (pintype "passive"))
      (node (ref "R188") (pin "1") (pinfunction "1_1") (pintype "passive"))
      (node (ref "R87") (pin "1") (pinfunction "1_1") (pintype "passive"))
      (node (ref "R88") (pin "1") (pinfunction "1_1") (pintype "passive"))
      (node (ref "R90") (pin "1") (pinfunction "1_1") (pintype "passive"))
      (node (ref "R91") (pin "2") (pinfunction "2_2") (pintype "passive"))
    )
    (net (code "55") (name "Net-(IC19H-IO_L58P_4)") (class "Default")
      (node (ref "IC19") (pin "L7") (pinfunction "IO_L58P_4_L7") (pintype "bidirectional"))
      (node (ref "R91") (pin "1") (pinfunction "1_1") (pintype "passive"))
    )
    (net (code "56") (name "P1V5") (class "Default")
      (node (ref "C103") (pin "2") (pinfunction "2_2") (pintype "passive"))
      (node (ref "C104") (pin "2") (pinfunction "2_2") (pintype "passive"))
      (node (ref "C105") (pin "2") (pinfunction "2_2") (pintype "passive"))
      (node (ref "C106") (pin "2") (pinfunction "2_2") (pintype "passive"))
      (node (ref "C107") (pin "2") (pinfunction "2_2") (pintype "passive"))
      (node (ref "C108") (pin "2") (pinfunction "2_2") (pintype "passive"))
      (node (ref "C109") (pin "2") (pinfunction "2_2") (pintype "passive"))
      (node (ref "C110") (pin "2") (pinfunction "2_2") (pintype "passive"))
      (node (ref "C111") (pin "2") (pinfunction "2_2") (pintype "passive"))
      (node (ref "IC4") (pin "A1") (pinfunction "VDDQ_A1") (pintype "power_in"))
      (node (ref "IC4") (pin "A8") (pinfunction "VDDQ_A8") (pintype "power_in"))
      (node (ref "IC4") (pin "B2") (pinfunction "VDD_B2") (pintype "power_in"))
      (node (ref "IC4") (pin "C1") (pinfunction "VDDQ_C1") (pintype "power_in"))
      (node (ref "IC4") (pin "C9") (pinfunction "VDDQ_C9") (pintype "power_in"))
      (node (ref "IC4") (pin "D2") (pinfunction "VDDQ_D2") (pintype "power_in"))
      (node (ref "IC4") (pin "D9") (pinfunction "VDD_D9") (pintype "power_in"))
      (node (ref "IC4") (pin "E9") (pinfunction "VDDQ_E9") (pintype "power_in"))
      (node (ref "IC4") (pin "F1") (pinfunction "VDDQ_F1") (pintype "power_in"))
      (node (ref "IC4") (pin "G7") (pinfunction "VDD_G7") (pintype "power_in"))
      (node (ref "IC4") (pin "H2") (pinfunction "VDDQ_H2") (pintype "power_in"))
      (node (ref "IC4") (pin "H9") (pinfunction "VDDQ_H9") (pintype "power_in"))
      (node (ref "IC4") (pin "K2") (pinfunction "VDD_K2") (pintype "power_in"))
      (node (ref "IC4") (pin "K8") (pinfunction "VDD_K8") (pintype "power_in"))
      (node (ref "IC4") (pin "N1") (pinfunction "VDD_N1") (pintype "power_in"))
      (node (ref "IC4") (pin "N9") (pinfunction "VDD_N9") (pintype "power_in"))
      (node (ref "IC4") (pin "R1") (pinfunction "VDD_R1") (pintype "power_in"))
      (node (ref "IC4") (pin "R9") (pinfunction "VDD_R9") (pintype "power_in"))
    )
    (net (code "57") (name "VREF_DDR3") (class "Default")
      (node (ref "C152") (pin "2") (pinfunction "2_2") (pintype "passive"))
      (node (ref "C20") (pin "2") (pinfunction "2_2") (pintype "passive"))
      (node (ref "C206") (pin "2") (pinfunction "2_2") (pintype "passive"))
      (node (ref "C235") (pin "2") (pinfunction "2_2") (pintype "passive"))
      (node (ref "C94") (pin "2") (pinfunction "2_2") (pintype "passive"))
      (node (ref "IC19") (pin "H6") (pinfunction "IO_L83N_VREF_4_H6") (pintype "bidirectional"))
      (node (ref "IC19") (pin "L6") (pinfunction "IO_L58N_VREF_4_L6") (pintype "bidirectional"))
      (node (ref "IC4") (pin "H1") (pinfunction "VREFDQ_H1") (pintype "power_in"))
      (node (ref "IC4") (pin "M8") (pinfunction "VREFCA_M8") (pintype "power_in"))
    )
    (net (code "58") (name "VTT_DDR3") (class "Default")
      (node (ref "C112") (pin "2") (pinfunction "2_2") (pintype "passive"))
      (node (ref "C113") (pin "2") (pinfunction "2_2") (pintype "passive"))
      (node (ref "C114") (pin "2") (pinfunction "2_2") (pintype "passive"))
      (node (ref "C115") (pin "2") (pinfunction "2_2") (pintype "passive"))
      (node (ref "C95") (pin "2") (pinfunction "2_2") (pintype "passive"))
      (node (ref "C96") (pin "2") (pinfunction "2_2") (pintype "passive"))
      (node (ref "C97") (pin "2") (pinfunction "2_2") (pintype "passive"))
      (node (ref "C98") (pin "2") (pinfunction "2_2") (pintype "passive"))
      (node (ref "C99") (pin "2") (pinfunction "2_2") (pintype "passive"))
      (node (ref "R39") (pin "2") (pinfunction "2_2") (pintype "passive"))
      (node (ref "R40") (pin "2") (pinfunction "2_2") (pintype "passive"))
      (node (ref "R41") (pin "2") (pinfunction "2_2") (pintype "passive"))
      (node (ref "R42") (pin "2") (pinfunction "2_2") (pintype "passive"))
      (node (ref "R43") (pin "2") (pinfunction "2_2") (pintype "passive"))
      (node (ref "R44") (pin "2") (pinfunction "2_2") (pintype "passive"))
      (node (ref "R45") (pin "2") (pinfunction "2_2") (pintype "passive"))
      (node (ref "R46") (pin "2") (pinfunction "2_2") (pintype "passive"))
      (node (ref "R47") (pin "2") (pinfunction "2_2") (pintype "passive"))
      (node (ref "R48") (pin "2") (pinfunction "2_2") (pintype "passive"))
      (node (ref "R49") (pin "2") (pinfunction "2_2") (pintype "passive"))
      (node (ref "R50") (pin "2") (pinfunction "2_2") (pintype "passive"))
      (node (ref "R52") (pin "2") (pinfunction "2_2") (pintype "passive"))
      (node (ref "R53") (pin "2") (pinfunction "2_2") (pintype "passive"))
      (node (ref "R54") (pin "2") (pinfunction "2_2") (pintype "passive"))
      (node (ref "R55") (pin "2") (pinfunction "2_2") (pintype "passive"))
      (node (ref "R56") (pin "2") (pinfunction "2_2") (pintype "passive"))
      (node (ref "R57") (pin "2") (pinfunction "2_2") (pintype "passive"))
      (node (ref "R58") (pin "2") (pinfunction "2_2") (pintype "passive"))
      (node (ref "R59") (pin "2") (pinfunction "2_2") (pintype "passive"))
      (node (ref "R61") (pin "2") (pinfunction "2_2") (pintype "passive"))
      (node (ref "R62") (pin "2") (pinfunction "2_2") (pintype "passive"))
      (node (ref "R63") (pin "2") (pinfunction "2_2") (pintype "passive"))
      (node (ref "R64") (pin "2") (pinfunction "2_2") (pintype "passive"))
      (node (ref "R65") (pin "2") (pinfunction "2_2") (pintype "passive"))
      (node (ref "R66") (pin "2") (pinfunction "2_2") (pintype "passive"))
      (node (ref "R67") (pin "2") (pinfunction "2_2") (pintype "passive"))
      (node (ref "R68") (pin "2") (pinfunction "2_2") (pintype "passive"))
      (node (ref "R69") (pin "2") (pinfunction "2_2") (pintype "passive"))
      (node (ref "R70") (pin "2") (pinfunction "2_2") (pintype "passive"))
      (node (ref "R71") (pin "2") (pinfunction "2_2") (pintype "passive"))
      (node (ref "R72") (pin "2") (pinfunction "2_2") (pintype "passive"))
      (node (ref "R73") (pin "2") (pinfunction "2_2") (pintype "passive"))
      (node (ref "R74") (pin "2") (pinfunction "2_2") (pintype "passive"))
      (node (ref "R75") (pin "2") (pinfunction "2_2") (pintype "passive"))
      (node (ref "R76") (pin "2") (pinfunction "2_2") (pintype "passive"))
      (node (ref "R77") (pin "2") (pinfunction "2_2") (pintype "passive"))
      (node (ref "R78") (pin "2") (pinfunction "2_2") (pintype "passive"))
      (node (ref "R79") (pin "2") (pinfunction "2_2") (pintype "passive"))
      (node (ref "R80") (pin "2") (pinfunction "2_2") (pintype "passive"))
      (node (ref "R81") (pin "2") (pinfunction "2_2") (pintype "passive"))
      (node (ref "R85") (pin "2") (pinfunction "2_2") (pintype "passive"))
      (node (ref "R94") (pin "2") (pinfunction "2_2") (pintype "passive"))
    )
    (net (code "59") (name "unconnected-(IC4-NC-PadJ1)") (class "Default")
      (node (ref "IC4") (pin "J1") (pinfunction "NC_J1") (pintype "passive+no_connect"))
    )
    (net (code "60") (name "unconnected-(IC4-NC-PadJ9)") (class "Default")
      (node (ref "IC4") (pin "J9") (pinfunction "NC_J9") (pintype "passive+no_connect"))
    )
    (net (code "61") (name "unconnected-(IC4-NC-PadL1)") (class "Default")
      (node (ref "IC4") (pin "L1") (pinfunction "NC_L1") (pintype "passive+no_connect"))
    )
    (net (code "62") (name "unconnected-(IC4-NC-PadL9)") (class "Default")
      (node (ref "IC4") (pin "L9") (pinfunction "NC_L9") (pintype "passive+no_connect"))
    )
    (net (code "63") (name "unconnected-(IC4-NC-PadM7)") (class "Default")
      (node (ref "IC4") (pin "M7") (pinfunction "NC_M7") (pintype "passive+no_connect"))
    )
    (net (code "64") (name "unconnected-(IC19H-IO_L83P_4-PadJ6)") (class "Default")
      (node (ref "IC19") (pin "J6") (pinfunction "IO_L83P_4_J6") (pintype "bidirectional"))
    )
  )
)
